# s2m.net
KiCad netlist of a schematic drawn in Altium Designer
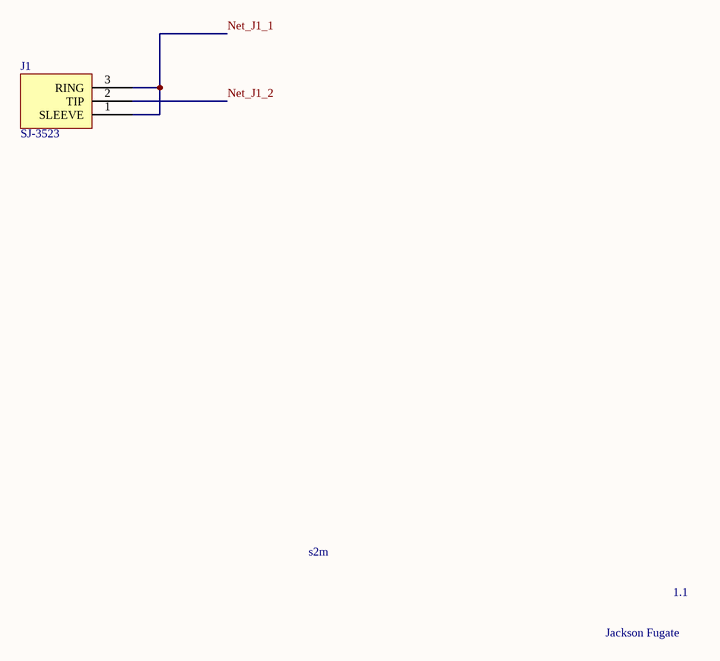
[diagram p0: s2m.SchDoc]

(export (version "E")
  (design (tool "Eeschema 10.0.6"))
  (components
    (comp (ref "J1")
      (value "SJ-3523")
      (footprint "SJ-352X")
      (libsource (lib "JF_master_lib") (part "SJ-3523"))
    )
  )
  (nets
    (net (code "1") (name "/Net_J1_1") (class "Default")
      (node (ref "J1") (pin "1") (pinfunction "SLEEVE_1") (pintype "passive"))
      (node (ref "J1") (pin "3") (pinfunction "RING_3") (pintype "passive"))
    )
    (net (code "2") (name "/Net_J1_2") (class "Default")
      (node (ref "J1") (pin "2") (pinfunction "TIP_2") (pintype "passive"))
    )
  )
)
